# Blinker_06.net
KiCad netlist of a schematic drawn in EAGLE
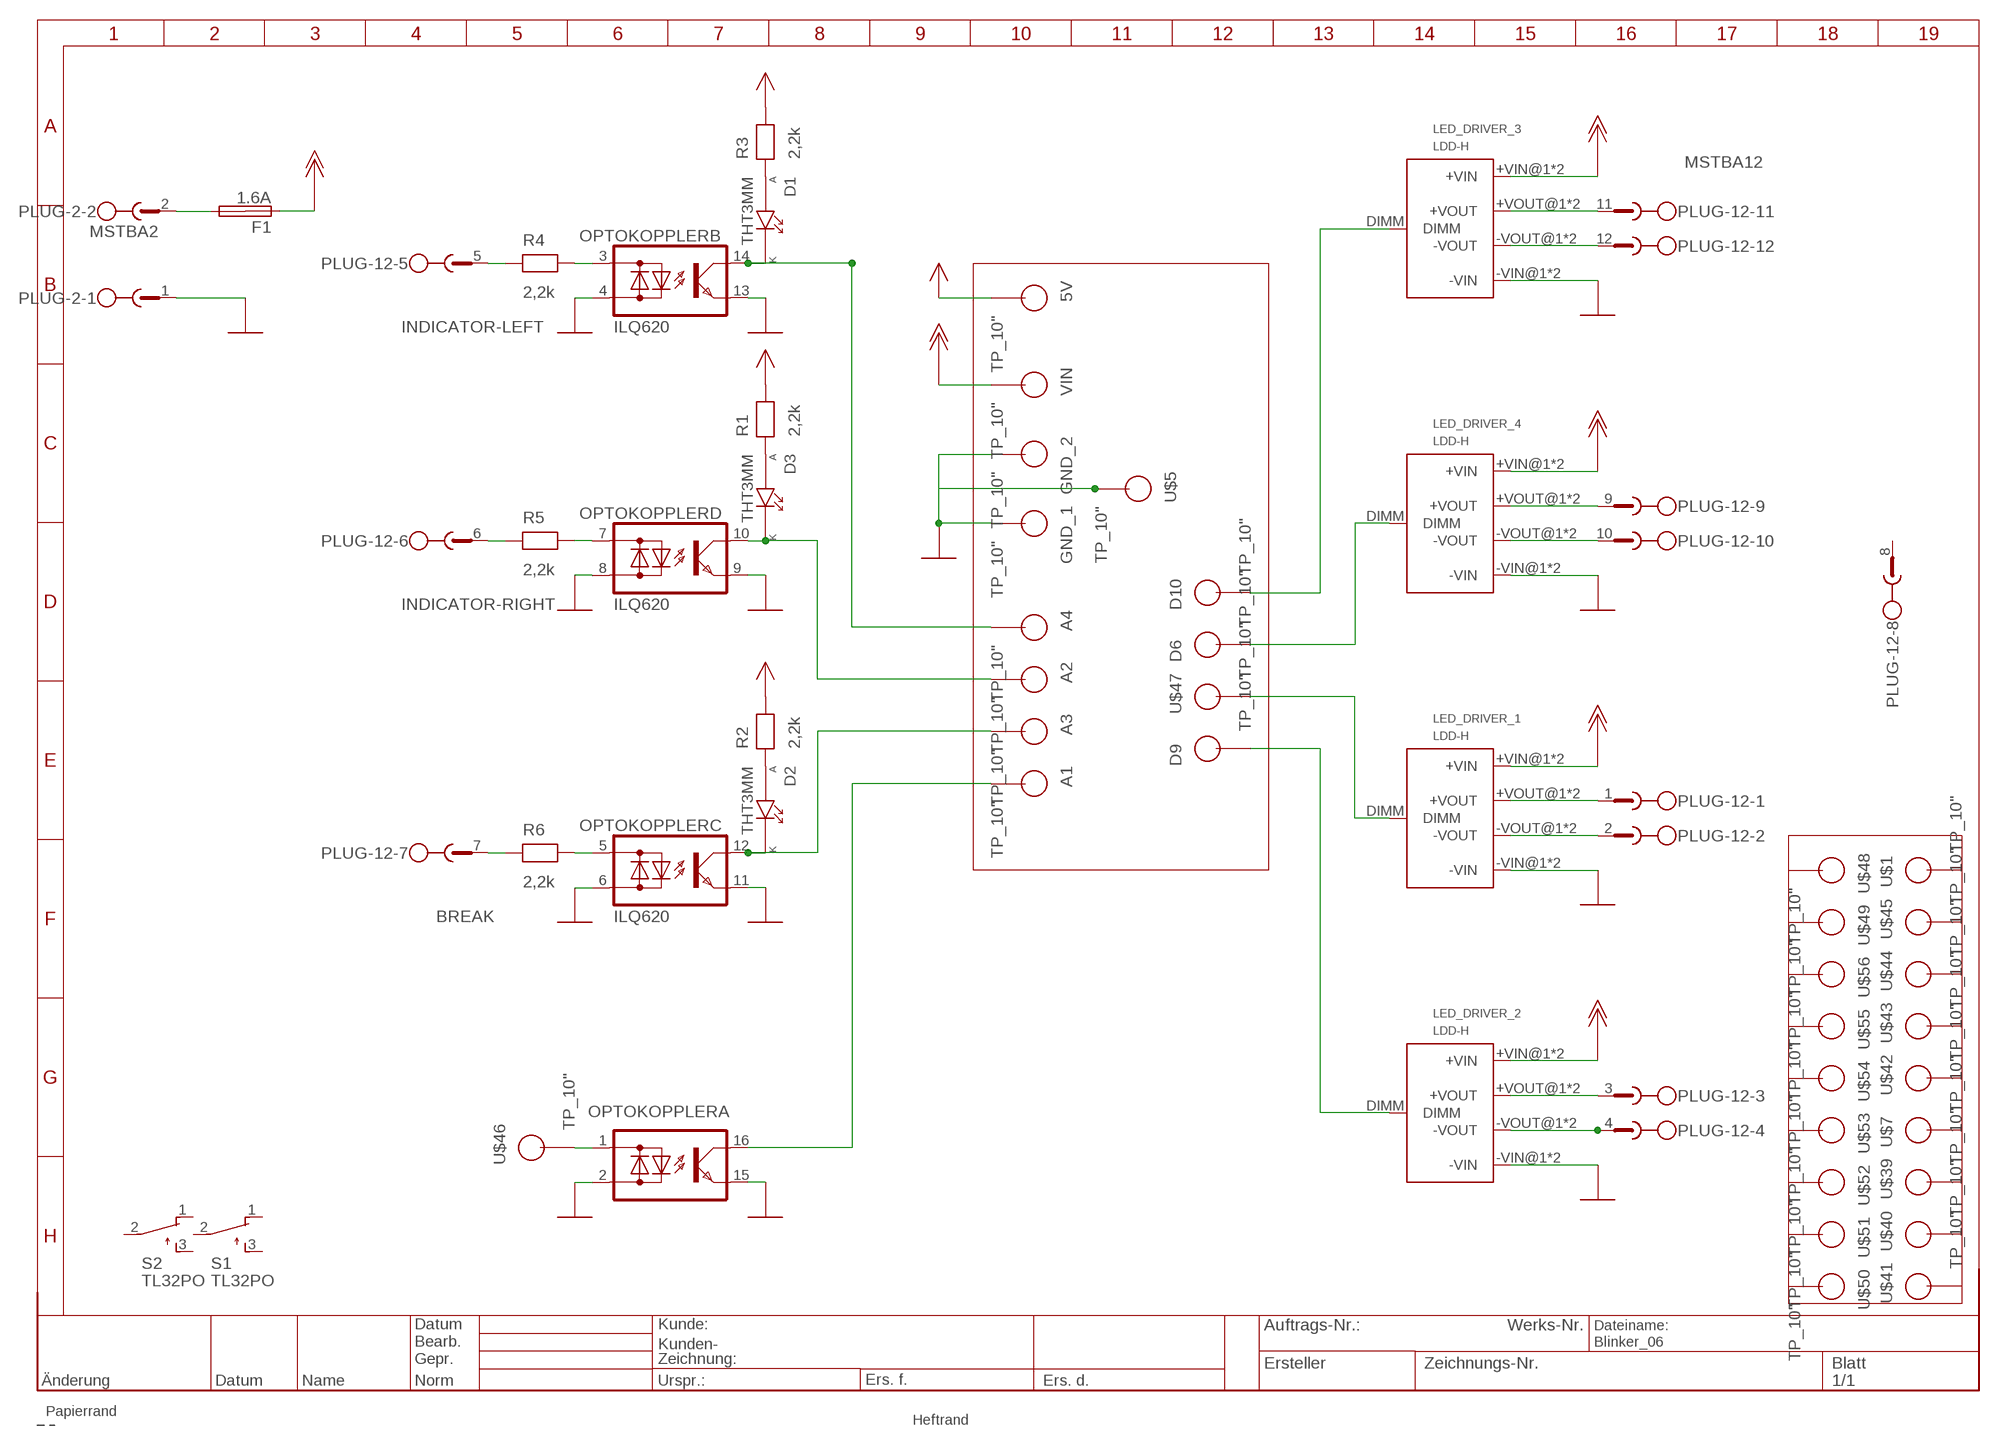
[diagram p0: schematic, sheet 1]

(export (version "E")
  (design (tool "Eeschema 10.0.6"))
  (components
    (comp (ref "5V")
      (value "TP_10\"")
      (footprint "eagle-import:TP_10")
      (libsource (lib "eagle-import") (part "TP_10{dblquote}"))
    )
    (comp (ref "A1")
      (value "TP_10\"")
      (footprint "eagle-import:TP_10")
      (libsource (lib "eagle-import") (part "TP_10{dblquote}"))
    )
    (comp (ref "A2")
      (value "TP_10\"")
      (footprint "eagle-import:TP_10")
      (libsource (lib "eagle-import") (part "TP_10{dblquote}"))
    )
    (comp (ref "A3")
      (value "TP_10\"")
      (footprint "eagle-import:TP_10")
      (libsource (lib "eagle-import") (part "TP_10{dblquote}"))
    )
    (comp (ref "A4")
      (value "TP_10\"")
      (footprint "eagle-import:TP_10")
      (libsource (lib "eagle-import") (part "TP_10{dblquote}"))
    )
    (comp (ref "D1")
      (value "THT3MM")
      (footprint "eagle-import:THT3MM")
      (libsource (lib "eagle-import") (part "THT3MM"))
    )
    (comp (ref "D2")
      (value "THT3MM")
      (footprint "eagle-import:THT3MM")
      (libsource (lib "eagle-import") (part "THT3MM"))
    )
    (comp (ref "D3")
      (value "THT3MM")
      (footprint "eagle-import:THT3MM")
      (libsource (lib "eagle-import") (part "THT3MM"))
    )
    (comp (ref "D6")
      (value "TP_10\"")
      (footprint "eagle-import:TP_10")
      (libsource (lib "eagle-import") (part "TP_10{dblquote}"))
    )
    (comp (ref "D9")
      (value "TP_10\"")
      (footprint "eagle-import:TP_10")
      (libsource (lib "eagle-import") (part "TP_10{dblquote}"))
    )
    (comp (ref "D10")
      (value "TP_10\"")
      (footprint "eagle-import:TP_10")
      (libsource (lib "eagle-import") (part "TP_10{dblquote}"))
    )
    (comp (ref "F1")
      (value "1.6A")
      (footprint "eagle-import:SHK20Q")
      (libsource (lib "eagle-import") (part "SHK20Q"))
    )
    (comp (ref "GND_1")
      (value "TP_10\"")
      (footprint "eagle-import:TP_10")
      (libsource (lib "eagle-import") (part "TP_10{dblquote}"))
    )
    (comp (ref "GND_2")
      (value "TP_10\"")
      (footprint "eagle-import:TP_10")
      (libsource (lib "eagle-import") (part "TP_10{dblquote}"))
    )
    (comp (ref "LED_DRIVER_1")
      (value "LDD-H")
      (footprint "eagle-import:LDD-H")
      (libsource (lib "eagle-import") (part "LDD-H"))
    )
    (comp (ref "LED_DRIVER_2")
      (value "LDD-H")
      (footprint "eagle-import:LDD-H")
      (libsource (lib "eagle-import") (part "LDD-H"))
    )
    (comp (ref "LED_DRIVER_3")
      (value "LDD-H")
      (footprint "eagle-import:LDD-H")
      (libsource (lib "eagle-import") (part "LDD-H"))
    )
    (comp (ref "LED_DRIVER_4")
      (value "LDD-H")
      (footprint "eagle-import:LDD-H")
      (libsource (lib "eagle-import") (part "LDD-H"))
    )
    (comp (ref "OPTOKOPPLER")
      (value "ILQ620")
      (footprint "eagle-import:DIL16")
      (libsource (lib "eagle-import") (part "ILQ620"))
    )
    (comp (ref "PLUG-2")
      (value "MSTBA2")
      (footprint "eagle-import:MSTBA2")
      (fields (field (name "MF") "FARNELL") (field (name "MPN") "1757242"))
      (libsource (lib "eagle-import") (part "MSTBA2"))
    )
    (comp (ref "PLUG-12")
      (value "MSTBA12")
      (footprint "eagle-import:MSTBA12")
      (fields (field (name "MPN") "1757349"))
      (libsource (lib "eagle-import") (part "MSTBA12"))
    )
    (comp (ref "R1")
      (value "2,2k")
      (footprint "eagle-import:R-10")
      (libsource (lib "eagle-import") (part "RESEU-10"))
    )
    (comp (ref "R2")
      (value "2,2k")
      (footprint "eagle-import:R-10")
      (libsource (lib "eagle-import") (part "RESEU-10"))
    )
    (comp (ref "R3")
      (value "2,2k")
      (footprint "eagle-import:R-10")
      (libsource (lib "eagle-import") (part "RESEU-10"))
    )
    (comp (ref "R4")
      (value "2,2k")
      (footprint "eagle-import:R-10")
      (libsource (lib "eagle-import") (part "RESEU-10"))
    )
    (comp (ref "R5")
      (value "2,2k")
      (footprint "eagle-import:R-10")
      (libsource (lib "eagle-import") (part "RESEU-10"))
    )
    (comp (ref "R6")
      (value "2,2k")
      (footprint "eagle-import:R-10")
      (libsource (lib "eagle-import") (part "RESEU-10"))
    )
    (comp (ref "S1")
      (value "TL32PO")
      (footprint "eagle-import:TL3XPO")
      (libsource (lib "eagle-import") (part "TL32PO"))
    )
    (comp (ref "S2")
      (value "TL32PO")
      (footprint "eagle-import:TL3XPO")
      (libsource (lib "eagle-import") (part "TL32PO"))
    )
    (comp (ref "U$1")
      (value "TP_10\"")
      (footprint "eagle-import:TP_10")
      (libsource (lib "eagle-import") (part "TP_10{dblquote}"))
    )
    (comp (ref "U$5")
      (value "TP_10\"")
      (footprint "eagle-import:TP_10")
      (libsource (lib "eagle-import") (part "TP_10{dblquote}"))
    )
    (comp (ref "U$7")
      (value "TP_10\"")
      (footprint "eagle-import:TP_10")
      (libsource (lib "eagle-import") (part "TP_10{dblquote}"))
    )
    (comp (ref "U$39")
      (value "TP_10\"")
      (footprint "eagle-import:TP_10")
      (libsource (lib "eagle-import") (part "TP_10{dblquote}"))
    )
    (comp (ref "U$40")
      (value "TP_10\"")
      (footprint "eagle-import:TP_10")
      (libsource (lib "eagle-import") (part "TP_10{dblquote}"))
    )
    (comp (ref "U$41")
      (value "TP_10\"")
      (footprint "eagle-import:TP_10")
      (libsource (lib "eagle-import") (part "TP_10{dblquote}"))
    )
    (comp (ref "U$42")
      (value "TP_10\"")
      (footprint "eagle-import:TP_10")
      (libsource (lib "eagle-import") (part "TP_10{dblquote}"))
    )
    (comp (ref "U$43")
      (value "TP_10\"")
      (footprint "eagle-import:TP_10")
      (libsource (lib "eagle-import") (part "TP_10{dblquote}"))
    )
    (comp (ref "U$44")
      (value "TP_10\"")
      (footprint "eagle-import:TP_10")
      (libsource (lib "eagle-import") (part "TP_10{dblquote}"))
    )
    (comp (ref "U$45")
      (value "TP_10\"")
      (footprint "eagle-import:TP_10")
      (libsource (lib "eagle-import") (part "TP_10{dblquote}"))
    )
    (comp (ref "U$46")
      (value "TP_10\"")
      (footprint "eagle-import:TP_10")
      (libsource (lib "eagle-import") (part "TP_10{dblquote}"))
    )
    (comp (ref "U$47")
      (value "TP_10\"")
      (footprint "eagle-import:TP_10")
      (libsource (lib "eagle-import") (part "TP_10{dblquote}"))
    )
    (comp (ref "U$48")
      (value "TP_10\"")
      (footprint "eagle-import:TP_10")
      (libsource (lib "eagle-import") (part "TP_10{dblquote}"))
    )
    (comp (ref "U$49")
      (value "TP_10\"")
      (footprint "eagle-import:TP_10")
      (libsource (lib "eagle-import") (part "TP_10{dblquote}"))
    )
    (comp (ref "U$50")
      (value "TP_10\"")
      (footprint "eagle-import:TP_10")
      (libsource (lib "eagle-import") (part "TP_10{dblquote}"))
    )
    (comp (ref "U$51")
      (value "TP_10\"")
      (footprint "eagle-import:TP_10")
      (libsource (lib "eagle-import") (part "TP_10{dblquote}"))
    )
    (comp (ref "U$52")
      (value "TP_10\"")
      (footprint "eagle-import:TP_10")
      (libsource (lib "eagle-import") (part "TP_10{dblquote}"))
    )
    (comp (ref "U$53")
      (value "TP_10\"")
      (footprint "eagle-import:TP_10")
      (libsource (lib "eagle-import") (part "TP_10{dblquote}"))
    )
    (comp (ref "U$54")
      (value "TP_10\"")
      (footprint "eagle-import:TP_10")
      (libsource (lib "eagle-import") (part "TP_10{dblquote}"))
    )
    (comp (ref "U$55")
      (value "TP_10\"")
      (footprint "eagle-import:TP_10")
      (libsource (lib "eagle-import") (part "TP_10{dblquote}"))
    )
    (comp (ref "U$56")
      (value "TP_10\"")
      (footprint "eagle-import:TP_10")
      (libsource (lib "eagle-import") (part "TP_10{dblquote}"))
    )
    (comp (ref "VIN")
      (value "TP_10\"")
      (footprint "eagle-import:TP_10")
      (libsource (lib "eagle-import") (part "TP_10{dblquote}"))
    )
  )
  (nets
    (net (code "1") (name "+5V") (class "Default")
      (node (ref "5V") (pin "P$1") (pinfunction "TP_13_P$1") (pintype "bidirectional"))
      (node (ref "R1") (pin "2") (pinfunction "2_2") (pintype "passive"))
      (node (ref "R2") (pin "2") (pinfunction "2_2") (pintype "passive"))
      (node (ref "R3") (pin "2") (pinfunction "2_2") (pintype "passive"))
    )
    (net (code "2") (name "+12V") (class "Default")
      (node (ref "F1") (pin "1A") (pinfunction "1A_1A") (pintype "passive"))
      (node (ref "LED_DRIVER_1") (pin "+VIN@1") (pinfunction "+VIN_+VIN@1") (pintype "power_in"))
      (node (ref "LED_DRIVER_1") (pin "+VIN@2") (pinfunction "+VIN_+VIN@2") (pintype "power_in"))
      (node (ref "LED_DRIVER_2") (pin "+VIN@1") (pinfunction "+VIN_+VIN@1") (pintype "power_in"))
      (node (ref "LED_DRIVER_2") (pin "+VIN@2") (pinfunction "+VIN_+VIN@2") (pintype "power_in"))
      (node (ref "LED_DRIVER_3") (pin "+VIN@1") (pinfunction "+VIN_+VIN@1") (pintype "power_in"))
      (node (ref "LED_DRIVER_3") (pin "+VIN@2") (pinfunction "+VIN_+VIN@2") (pintype "power_in"))
      (node (ref "LED_DRIVER_4") (pin "+VIN@1") (pinfunction "+VIN_+VIN@1") (pintype "power_in"))
      (node (ref "LED_DRIVER_4") (pin "+VIN@2") (pinfunction "+VIN_+VIN@2") (pintype "power_in"))
      (node (ref "VIN") (pin "P$1") (pinfunction "TP_13_P$1") (pintype "bidirectional"))
    )
    (net (code "3") (name "/BREAK") (class "Default")
      (node (ref "PLUG-12") (pin "7") (pinfunction "1_7") (pintype "passive"))
      (node (ref "R6") (pin "1") (pinfunction "1_1") (pintype "passive"))
    )
    (net (code "4") (name "/INDICATOR-LEFT") (class "Default")
      (node (ref "PLUG-12") (pin "5") (pinfunction "1_5") (pintype "passive"))
      (node (ref "R4") (pin "1") (pinfunction "1_1") (pintype "passive"))
    )
    (net (code "5") (name "/INDICATOR-RIGHT") (class "Default")
      (node (ref "PLUG-12") (pin "6") (pinfunction "1_6") (pintype "passive"))
      (node (ref "R5") (pin "1") (pinfunction "1_1") (pintype "passive"))
    )
    (net (code "6") (name "GND") (class "Default")
      (node (ref "GND_1") (pin "P$1") (pinfunction "TP_13_P$1") (pintype "bidirectional"))
      (node (ref "GND_2") (pin "P$1") (pinfunction "TP_13_P$1") (pintype "bidirectional"))
      (node (ref "LED_DRIVER_1") (pin "-VIN@1") (pinfunction "-VIN_-VIN@1") (pintype "power_in"))
      (node (ref "LED_DRIVER_1") (pin "-VIN@2") (pinfunction "-VIN_-VIN@2") (pintype "power_in"))
      (node (ref "LED_DRIVER_2") (pin "-VIN@1") (pinfunction "-VIN_-VIN@1") (pintype "power_in"))
      (node (ref "LED_DRIVER_2") (pin "-VIN@2") (pinfunction "-VIN_-VIN@2") (pintype "power_in"))
      (node (ref "LED_DRIVER_3") (pin "-VIN@1") (pinfunction "-VIN_-VIN@1") (pintype "power_in"))
      (node (ref "LED_DRIVER_3") (pin "-VIN@2") (pinfunction "-VIN_-VIN@2") (pintype "power_in"))
      (node (ref "LED_DRIVER_4") (pin "-VIN@1") (pinfunction "-VIN_-VIN@1") (pintype "power_in"))
      (node (ref "LED_DRIVER_4") (pin "-VIN@2") (pinfunction "-VIN_-VIN@2") (pintype "power_in"))
      (node (ref "OPTOKOPPLER") (pin "11") (pinfunction "E_11") (pintype "passive"))
      (node (ref "OPTOKOPPLER") (pin "13") (pinfunction "E_13") (pintype "passive"))
      (node (ref "OPTOKOPPLER") (pin "15") (pinfunction "E_15") (pintype "passive"))
      (node (ref "OPTOKOPPLER") (pin "2") (pinfunction "AC2_2") (pintype "passive"))
      (node (ref "OPTOKOPPLER") (pin "4") (pinfunction "AC2_4") (pintype "passive"))
      (node (ref "OPTOKOPPLER") (pin "6") (pinfunction "AC2_6") (pintype "passive"))
      (node (ref "OPTOKOPPLER") (pin "8") (pinfunction "AC2_8") (pintype "passive"))
      (node (ref "OPTOKOPPLER") (pin "9") (pinfunction "E_9") (pintype "passive"))
      (node (ref "PLUG-2") (pin "1") (pinfunction "1_1") (pintype "passive"))
      (node (ref "U$5") (pin "P$1") (pinfunction "TP_13_P$1") (pintype "bidirectional"))
    )
    (net (code "7") (name "Net-(A1-TP_13)") (class "Default")
      (node (ref "A1") (pin "P$1") (pinfunction "TP_13_P$1") (pintype "bidirectional"))
      (node (ref "OPTOKOPPLER") (pin "16") (pinfunction "C_16") (pintype "passive"))
    )
    (net (code "8") (name "Net-(A2-TP_13)") (class "Default")
      (node (ref "A2") (pin "P$1") (pinfunction "TP_13_P$1") (pintype "bidirectional"))
      (node (ref "D3") (pin "K") (pinfunction "P2K_K") (pintype "bidirectional"))
      (node (ref "OPTOKOPPLER") (pin "10") (pinfunction "C_10") (pintype "passive"))
    )
    (net (code "9") (name "Net-(A3-TP_13)") (class "Default")
      (node (ref "A3") (pin "P$1") (pinfunction "TP_13_P$1") (pintype "bidirectional"))
      (node (ref "D2") (pin "K") (pinfunction "P2K_K") (pintype "bidirectional"))
      (node (ref "OPTOKOPPLER") (pin "12") (pinfunction "C_12") (pintype "passive"))
    )
    (net (code "10") (name "Net-(A4-TP_13)") (class "Default")
      (node (ref "A4") (pin "P$1") (pinfunction "TP_13_P$1") (pintype "bidirectional"))
      (node (ref "D1") (pin "K") (pinfunction "P2K_K") (pintype "bidirectional"))
      (node (ref "OPTOKOPPLER") (pin "14") (pinfunction "C_14") (pintype "passive"))
    )
    (net (code "11") (name "Net-(D1-P1A)") (class "Default")
      (node (ref "D1") (pin "A") (pinfunction "P1A_A") (pintype "bidirectional"))
      (node (ref "R3") (pin "1") (pinfunction "1_1") (pintype "passive"))
    )
    (net (code "12") (name "Net-(D2-P1A)") (class "Default")
      (node (ref "D2") (pin "A") (pinfunction "P1A_A") (pintype "bidirectional"))
      (node (ref "R2") (pin "1") (pinfunction "1_1") (pintype "passive"))
    )
    (net (code "13") (name "Net-(D3-P1A)") (class "Default")
      (node (ref "D3") (pin "A") (pinfunction "P1A_A") (pintype "bidirectional"))
      (node (ref "R1") (pin "1") (pinfunction "1_1") (pintype "passive"))
    )
    (net (code "14") (name "Net-(D6-TP_13)") (class "Default")
      (node (ref "D6") (pin "P$1") (pinfunction "TP_13_P$1") (pintype "bidirectional"))
      (node (ref "LED_DRIVER_4") (pin "DIMM") (pinfunction "DIMM_DIMM") (pintype "input"))
    )
    (net (code "15") (name "Net-(D9-TP_13)") (class "Default")
      (node (ref "D9") (pin "P$1") (pinfunction "TP_13_P$1") (pintype "bidirectional"))
      (node (ref "LED_DRIVER_2") (pin "DIMM") (pinfunction "DIMM_DIMM") (pintype "input"))
    )
    (net (code "16") (name "Net-(D10-TP_13)") (class "Default")
      (node (ref "D10") (pin "P$1") (pinfunction "TP_13_P$1") (pintype "bidirectional"))
      (node (ref "LED_DRIVER_3") (pin "DIMM") (pinfunction "DIMM_DIMM") (pintype "input"))
    )
    (net (code "17") (name "Net-(LED_DRIVER_1-+VOUT-Pad+VOUT@1)") (class "Default")
      (node (ref "LED_DRIVER_1") (pin "+VOUT@1") (pinfunction "+VOUT_+VOUT@1") (pintype "output"))
      (node (ref "LED_DRIVER_1") (pin "+VOUT@2") (pinfunction "+VOUT_+VOUT@2") (pintype "output"))
      (node (ref "PLUG-12") (pin "1") (pinfunction "1_1") (pintype "passive"))
    )
    (net (code "18") (name "Net-(OPTOKOPPLERA-AC1)") (class "Default")
      (node (ref "OPTOKOPPLER") (pin "1") (pinfunction "AC1_1") (pintype "passive"))
      (node (ref "U$46") (pin "P$1") (pinfunction "TP_13_P$1") (pintype "bidirectional"))
    )
    (net (code "19") (name "Net-(OPTOKOPPLERB-AC1)") (class "Default")
      (node (ref "OPTOKOPPLER") (pin "3") (pinfunction "AC1_3") (pintype "passive"))
      (node (ref "R4") (pin "2") (pinfunction "2_2") (pintype "passive"))
    )
    (net (code "20") (name "Net-(OPTOKOPPLERC-AC1)") (class "Default")
      (node (ref "OPTOKOPPLER") (pin "5") (pinfunction "AC1_5") (pintype "passive"))
      (node (ref "R6") (pin "2") (pinfunction "2_2") (pintype "passive"))
    )
    (net (code "21") (name "Net-(OPTOKOPPLERD-AC1)") (class "Default")
      (node (ref "OPTOKOPPLER") (pin "7") (pinfunction "AC1_7") (pintype "passive"))
      (node (ref "R5") (pin "2") (pinfunction "2_2") (pintype "passive"))
    )
    (net (code "22") (name "Net-(PLUG-2B-1)") (class "Default")
      (node (ref "F1") (pin "2A") (pinfunction "2A_2A") (pintype "passive"))
      (node (ref "PLUG-2") (pin "2") (pinfunction "1_2") (pintype "passive"))
    )
    (net (code "23") (name "Net-(PLUG-12B-1)") (class "Default")
      (node (ref "LED_DRIVER_4") (pin "-VOUT@1") (pinfunction "-VOUT_-VOUT@1") (pintype "output"))
      (node (ref "LED_DRIVER_4") (pin "-VOUT@2") (pinfunction "-VOUT_-VOUT@2") (pintype "output"))
      (node (ref "PLUG-12") (pin "10") (pinfunction "1_10") (pintype "passive"))
    )
    (net (code "24") (name "Net-(PLUG-12C-1)") (class "Default")
      (node (ref "LED_DRIVER_3") (pin "+VOUT@1") (pinfunction "+VOUT_+VOUT@1") (pintype "output"))
      (node (ref "LED_DRIVER_3") (pin "+VOUT@2") (pinfunction "+VOUT_+VOUT@2") (pintype "output"))
      (node (ref "PLUG-12") (pin "11") (pinfunction "1_11") (pintype "passive"))
    )
    (net (code "25") (name "Net-(PLUG-12D-1)") (class "Default")
      (node (ref "LED_DRIVER_3") (pin "-VOUT@1") (pinfunction "-VOUT_-VOUT@1") (pintype "output"))
      (node (ref "LED_DRIVER_3") (pin "-VOUT@2") (pinfunction "-VOUT_-VOUT@2") (pintype "output"))
      (node (ref "PLUG-12") (pin "12") (pinfunction "1_12") (pintype "passive"))
    )
    (net (code "26") (name "Net-(PLUG-12E-1)") (class "Default")
      (node (ref "LED_DRIVER_1") (pin "-VOUT@1") (pinfunction "-VOUT_-VOUT@1") (pintype "output"))
      (node (ref "LED_DRIVER_1") (pin "-VOUT@2") (pinfunction "-VOUT_-VOUT@2") (pintype "output"))
      (node (ref "PLUG-12") (pin "2") (pinfunction "1_2") (pintype "passive"))
    )
    (net (code "27") (name "Net-(PLUG-12F-1)") (class "Default")
      (node (ref "LED_DRIVER_2") (pin "+VOUT@1") (pinfunction "+VOUT_+VOUT@1") (pintype "output"))
      (node (ref "LED_DRIVER_2") (pin "+VOUT@2") (pinfunction "+VOUT_+VOUT@2") (pintype "output"))
      (node (ref "PLUG-12") (pin "3") (pinfunction "1_3") (pintype "passive"))
    )
    (net (code "28") (name "Net-(PLUG-12G-1)") (class "Default")
      (node (ref "LED_DRIVER_2") (pin "-VOUT@1") (pinfunction "-VOUT_-VOUT@1") (pintype "output"))
      (node (ref "LED_DRIVER_2") (pin "-VOUT@2") (pinfunction "-VOUT_-VOUT@2") (pintype "output"))
      (node (ref "PLUG-12") (pin "4") (pinfunction "1_4") (pintype "passive"))
    )
    (net (code "29") (name "Net-(PLUG-12L-1)") (class "Default")
      (node (ref "LED_DRIVER_4") (pin "+VOUT@1") (pinfunction "+VOUT_+VOUT@1") (pintype "output"))
      (node (ref "LED_DRIVER_4") (pin "+VOUT@2") (pinfunction "+VOUT_+VOUT@2") (pintype "output"))
      (node (ref "PLUG-12") (pin "9") (pinfunction "1_9") (pintype "passive"))
    )
    (net (code "30") (name "Net-(U$47-TP_13)") (class "Default")
      (node (ref "LED_DRIVER_1") (pin "DIMM") (pinfunction "DIMM_DIMM") (pintype "input"))
      (node (ref "U$47") (pin "P$1") (pinfunction "TP_13_P$1") (pintype "bidirectional"))
    )
    (net (code "31") (name "unconnected-(F1-Pad1B)") (class "Default")
      (node (ref "F1") (pin "1B") (pinfunction "1B_1B") (pintype "passive"))
    )
    (net (code "32") (name "unconnected-(F1-Pad2B)") (class "Default")
      (node (ref "F1") (pin "2B") (pinfunction "2B_2B") (pintype "passive"))
    )
    (net (code "33") (name "unconnected-(PLUG-12K-1-Pad8)") (class "Default")
      (node (ref "PLUG-12") (pin "8") (pinfunction "1_8") (pintype "passive"))
    )
    (net (code "34") (name "unconnected-(S1-O-Pad1)") (class "Default")
      (node (ref "S1") (pin "1") (pinfunction "O_1") (pintype "passive"))
    )
    (net (code "35") (name "unconnected-(S1-P-Pad2)") (class "Default")
      (node (ref "S1") (pin "2") (pinfunction "P_2") (pintype "passive"))
    )
    (net (code "36") (name "unconnected-(S1-S-Pad3)") (class "Default")
      (node (ref "S1") (pin "3") (pinfunction "S_3") (pintype "passive"))
    )
    (net (code "37") (name "unconnected-(S2-O-Pad1)") (class "Default")
      (node (ref "S2") (pin "1") (pinfunction "O_1") (pintype "passive"))
    )
    (net (code "38") (name "unconnected-(S2-P-Pad2)") (class "Default")
      (node (ref "S2") (pin "2") (pinfunction "P_2") (pintype "passive"))
    )
    (net (code "39") (name "unconnected-(S2-S-Pad3)") (class "Default")
      (node (ref "S2") (pin "3") (pinfunction "S_3") (pintype "passive"))
    )
    (net (code "40") (name "unconnected-(U$1-TP_13-PadP$1)") (class "Default")
      (node (ref "U$1") (pin "P$1") (pinfunction "TP_13_P$1") (pintype "bidirectional"))
    )
    (net (code "41") (name "unconnected-(U$7-TP_13-PadP$1)") (class "Default")
      (node (ref "U$7") (pin "P$1") (pinfunction "TP_13_P$1") (pintype "bidirectional"))
    )
    (net (code "42") (name "unconnected-(U$39-TP_13-PadP$1)") (class "Default")
      (node (ref "U$39") (pin "P$1") (pinfunction "TP_13_P$1") (pintype "bidirectional"))
    )
    (net (code "43") (name "unconnected-(U$40-TP_13-PadP$1)") (class "Default")
      (node (ref "U$40") (pin "P$1") (pinfunction "TP_13_P$1") (pintype "bidirectional"))
    )
    (net (code "44") (name "unconnected-(U$41-TP_13-PadP$1)") (class "Default")
      (node (ref "U$41") (pin "P$1") (pinfunction "TP_13_P$1") (pintype "bidirectional"))
    )
    (net (code "45") (name "unconnected-(U$42-TP_13-PadP$1)") (class "Default")
      (node (ref "U$42") (pin "P$1") (pinfunction "TP_13_P$1") (pintype "bidirectional"))
    )
    (net (code "46") (name "unconnected-(U$43-TP_13-PadP$1)") (class "Default")
      (node (ref "U$43") (pin "P$1") (pinfunction "TP_13_P$1") (pintype "bidirectional"))
    )
    (net (code "47") (name "unconnected-(U$44-TP_13-PadP$1)") (class "Default")
      (node (ref "U$44") (pin "P$1") (pinfunction "TP_13_P$1") (pintype "bidirectional"))
    )
    (net (code "48") (name "unconnected-(U$45-TP_13-PadP$1)") (class "Default")
      (node (ref "U$45") (pin "P$1") (pinfunction "TP_13_P$1") (pintype "bidirectional"))
    )
    (net (code "49") (name "unconnected-(U$48-TP_13-PadP$1)") (class "Default")
      (node (ref "U$48") (pin "P$1") (pinfunction "TP_13_P$1") (pintype "bidirectional"))
    )
    (net (code "50") (name "unconnected-(U$49-TP_13-PadP$1)") (class "Default")
      (node (ref "U$49") (pin "P$1") (pinfunction "TP_13_P$1") (pintype "bidirectional"))
    )
    (net (code "51") (name "unconnected-(U$50-TP_13-PadP$1)") (class "Default")
      (node (ref "U$50") (pin "P$1") (pinfunction "TP_13_P$1") (pintype "bidirectional"))
    )
    (net (code "52") (name "unconnected-(U$51-TP_13-PadP$1)") (class "Default")
      (node (ref "U$51") (pin "P$1") (pinfunction "TP_13_P$1") (pintype "bidirectional"))
    )
    (net (code "53") (name "unconnected-(U$52-TP_13-PadP$1)") (class "Default")
      (node (ref "U$52") (pin "P$1") (pinfunction "TP_13_P$1") (pintype "bidirectional"))
    )
    (net (code "54") (name "unconnected-(U$53-TP_13-PadP$1)") (class "Default")
      (node (ref "U$53") (pin "P$1") (pinfunction "TP_13_P$1") (pintype "bidirectional"))
    )
    (net (code "55") (name "unconnected-(U$54-TP_13-PadP$1)") (class "Default")
      (node (ref "U$54") (pin "P$1") (pinfunction "TP_13_P$1") (pintype "bidirectional"))
    )
    (net (code "56") (name "unconnected-(U$55-TP_13-PadP$1)") (class "Default")
      (node (ref "U$55") (pin "P$1") (pinfunction "TP_13_P$1") (pintype "bidirectional"))
    )
    (net (code "57") (name "unconnected-(U$56-TP_13-PadP$1)") (class "Default")
      (node (ref "U$56") (pin "P$1") (pinfunction "TP_13_P$1") (pintype "bidirectional"))
    )
  )
)
